# ReflowOvenController.net
KiCad netlist of a schematic drawn in EAGLE
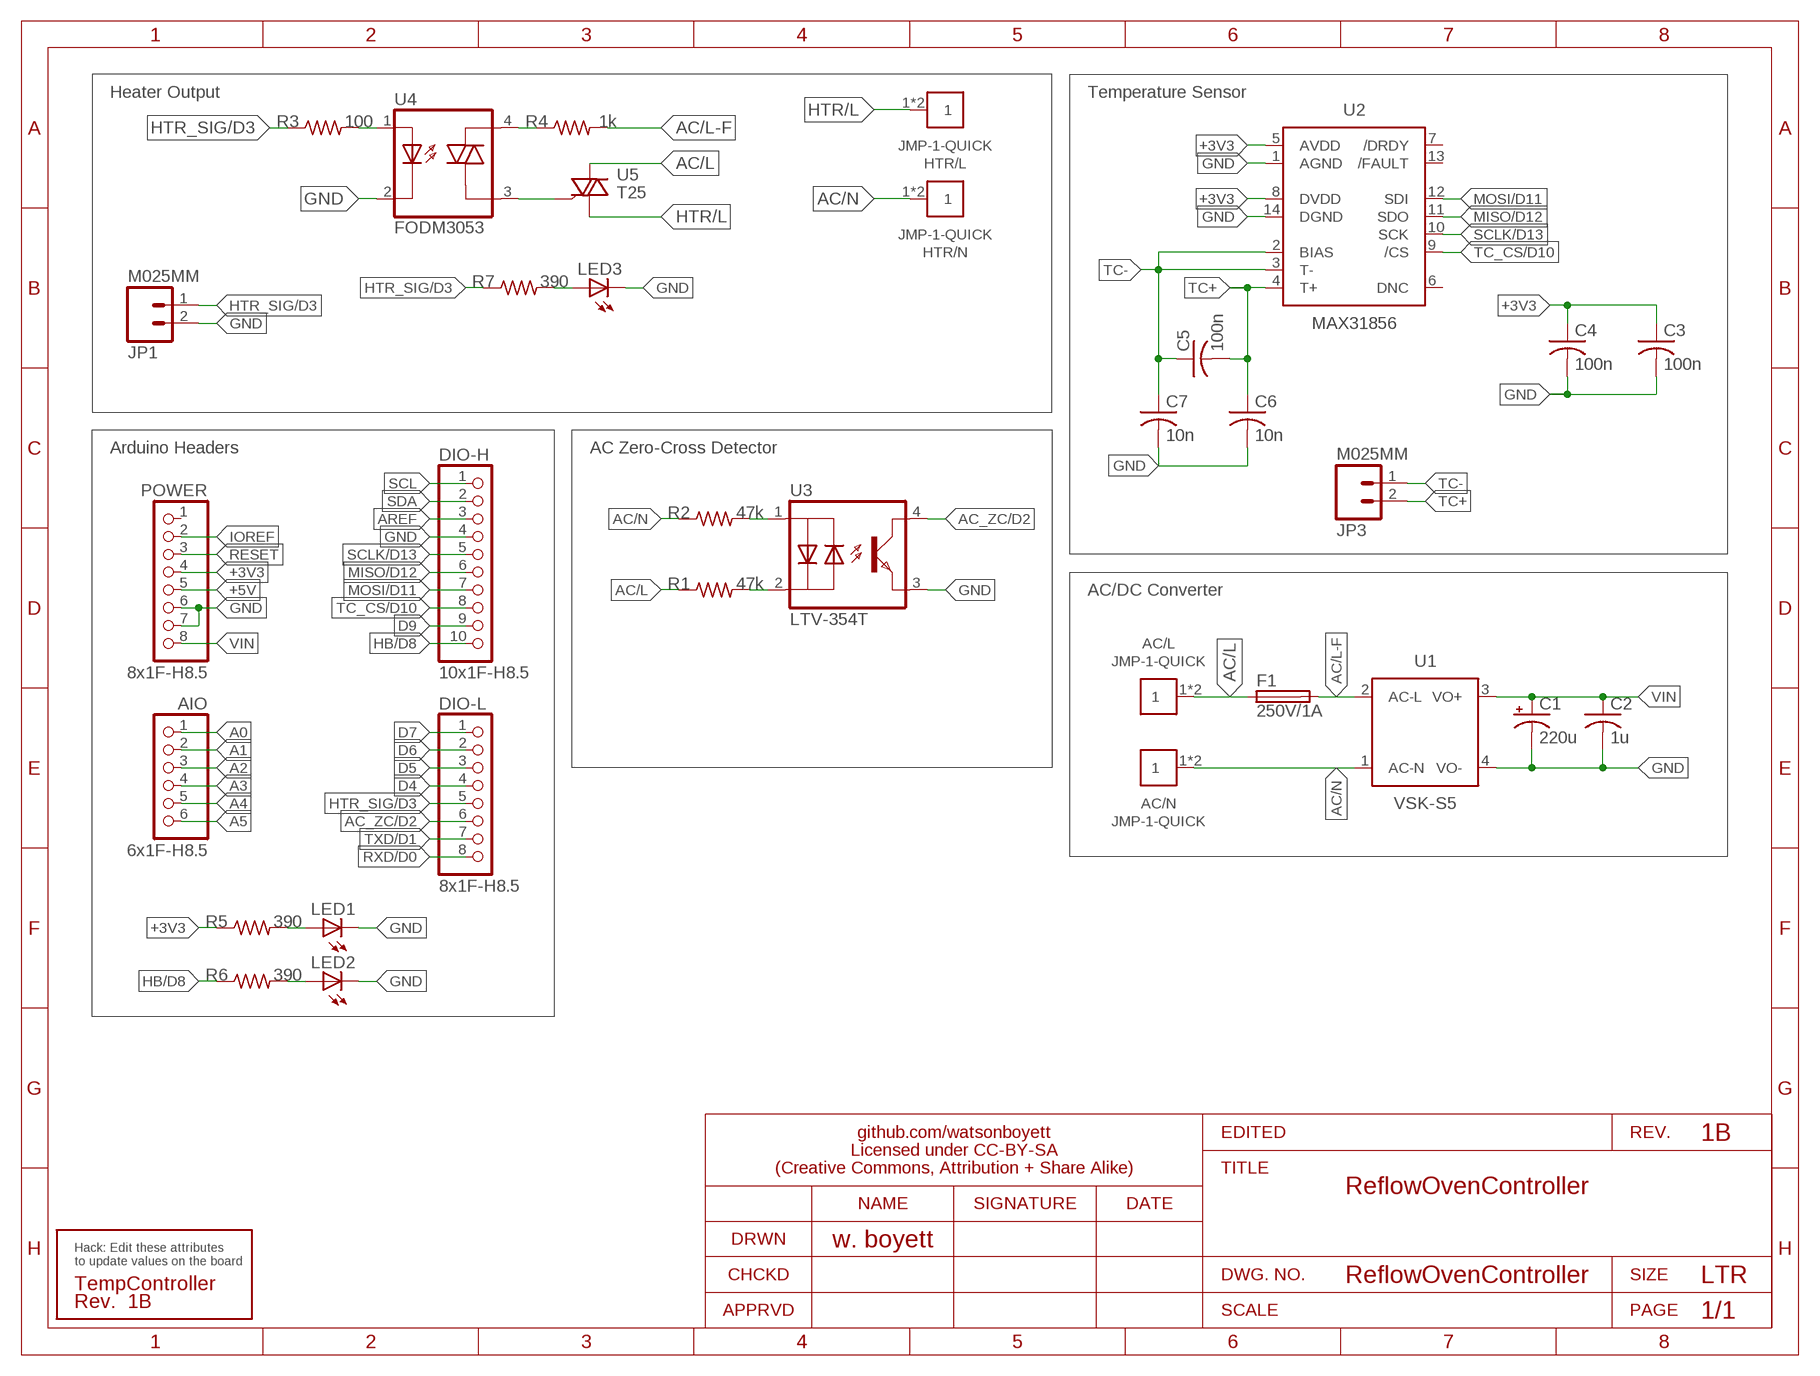
[diagram p0: schematic, sheet 1]

(export (version "E")
  (design (tool "Eeschema 10.0.6"))
  (components
    (comp (ref "AC/L")
      (value "JMP-1-QUICK")
      (footprint "eagle-import:QUICK-1")
      (fields (field (name "MPN") "1287"))
      (libsource (lib "eagle-import") (part "JMP-1-QUICK"))
    )
    (comp (ref "AC/N")
      (value "JMP-1-QUICK")
      (footprint "eagle-import:QUICK-1")
      (fields (field (name "MPN") "1287"))
      (libsource (lib "eagle-import") (part "JMP-1-QUICK"))
    )
    (comp (ref "AIO")
      (value "6x1F-H8.5")
      (footprint "eagle-import:1X06")
      (libsource (lib "eagle-import") (part "PINHD-1X6TH"))
    )
    (comp (ref "C1")
      (value "220u")
      (footprint "eagle-import:153CLV-1014")
      (libsource (lib "eagle-import") (part "CPOL-US153CLV-1014"))
    )
    (comp (ref "C2")
      (value "1u")
      (footprint "eagle-import:C0805")
      (libsource (lib "eagle-import") (part "C-USC0805"))
    )
    (comp (ref "C3")
      (value "100n")
      (footprint "eagle-import:C0805")
      (libsource (lib "eagle-import") (part "C-USC0805"))
    )
    (comp (ref "C4")
      (value "100n")
      (footprint "eagle-import:C0805")
      (libsource (lib "eagle-import") (part "C-USC0805"))
    )
    (comp (ref "C5")
      (value "100n")
      (footprint "eagle-import:C0805")
      (libsource (lib "eagle-import") (part "C-USC0805"))
    )
    (comp (ref "C6")
      (value "10n")
      (footprint "eagle-import:C0805")
      (libsource (lib "eagle-import") (part "C-USC0805"))
    )
    (comp (ref "C7")
      (value "10n")
      (footprint "eagle-import:C0805")
      (libsource (lib "eagle-import") (part "C-USC0805"))
    )
    (comp (ref "DIO-H")
      (value "10x1F-H8.5")
      (footprint "eagle-import:1X10")
      (libsource (lib "eagle-import") (part "PINHD-1X10TH"))
    )
    (comp (ref "DIO-L")
      (value "8x1F-H8.5")
      (footprint "eagle-import:1X08")
      (libsource (lib "eagle-import") (part "PINHD-1X8TH"))
    )
    (comp (ref "F1")
      (value "250V/1A")
      (footprint "eagle-import:2SMD-2410")
      (fields
        (field (name "MPN") "0452004.MRL")
        (field (name "MPN_1") "0454001.MR")
        (field (name "PN-DK") "F3144CT-ND")
      )
      (libsource (lib "eagle-import") (part "FUSE2410"))
    )
    (comp (ref "HTR/L")
      (value "JMP-1-QUICK")
      (footprint "eagle-import:QUICK-1")
      (fields (field (name "MPN") "1287"))
      (libsource (lib "eagle-import") (part "JMP-1-QUICK"))
    )
    (comp (ref "HTR/N")
      (value "JMP-1-QUICK")
      (footprint "eagle-import:QUICK-1")
      (fields (field (name "MPN") "1287"))
      (libsource (lib "eagle-import") (part "JMP-1-QUICK"))
    )
    (comp (ref "JP1")
      (value "M025MM")
      (footprint "eagle-import:SCREWTERMINAL-5MM-2")
      (fields (field (name "MPN") "1729128"))
      (libsource (lib "eagle-import") (part "M025MM"))
    )
    (comp (ref "JP3")
      (value "M025MM")
      (footprint "eagle-import:SCREWTERMINAL-5MM-2")
      (fields (field (name "MPN") "1729128"))
      (libsource (lib "eagle-import") (part "M025MM"))
    )
    (comp (ref "LED1")
      (value "LEDCHIP-LED0805")
      (footprint "eagle-import:CHIP-LED0805")
      (fields (field (name "MPN") "SML-LXT0805IW-TR"))
      (libsource (lib "eagle-import") (part "LEDCHIP-LED0805"))
    )
    (comp (ref "LED2")
      (value "LEDCHIP-LED0805")
      (footprint "eagle-import:CHIP-LED0805")
      (fields (field (name "MPN") "SML-LXT0805IW-TR"))
      (libsource (lib "eagle-import") (part "LEDCHIP-LED0805"))
    )
    (comp (ref "LED3")
      (value "LEDCHIP-LED0805")
      (footprint "eagle-import:CHIP-LED0805")
      (fields (field (name "MPN") "SML-LXT0805IW-TR"))
      (libsource (lib "eagle-import") (part "LEDCHIP-LED0805"))
    )
    (comp (ref "POWER")
      (value "8x1F-H8.5")
      (footprint "eagle-import:1X08")
      (libsource (lib "eagle-import") (part "PINHD-1X8TH"))
    )
    (comp (ref "R1")
      (value "47k")
      (footprint "eagle-import:R1206")
      (libsource (lib "eagle-import") (part "R-US_R1206"))
    )
    (comp (ref "R2")
      (value "47k")
      (footprint "eagle-import:R1206")
      (libsource (lib "eagle-import") (part "R-US_R1206"))
    )
    (comp (ref "R3")
      (value "100")
      (footprint "eagle-import:R0805")
      (libsource (lib "eagle-import") (part "R-US_R0805"))
    )
    (comp (ref "R4")
      (value "1k")
      (footprint "eagle-import:R1206")
      (libsource (lib "eagle-import") (part "R-US_R1206"))
    )
    (comp (ref "R5")
      (value "390")
      (footprint "eagle-import:R0805")
      (libsource (lib "eagle-import") (part "SmslsTron_R-US_R0805"))
    )
    (comp (ref "R6")
      (value "390")
      (footprint "eagle-import:R0805")
      (libsource (lib "eagle-import") (part "SmslsTron_R-US_R0805"))
    )
    (comp (ref "R7")
      (value "390")
      (footprint "eagle-import:R0805")
      (libsource (lib "eagle-import") (part "SmslsTron_R-US_R0805"))
    )
    (comp (ref "U$1")
      (value "SILK_QC")
      (footprint "eagle-import:SILK_QC")
      (fields (field (name "MPN") "DNP") (field (name "PRODUCT") "TempController") (field (name "REV") "1B"))
      (libsource (lib "eagle-import") (part "SILK_QC"))
    )
    (comp (ref "U1")
      (value "VSK-S5")
      (footprint "eagle-import:VSK-S5")
      (libsource (lib "eagle-import") (part "VSK-S5"))
    )
    (comp (ref "U2")
      (value "MAX31856")
      (footprint "eagle-import:TSSOP14")
      (fields (field (name "MPN") "MAX31856MUD+"))
      (libsource (lib "eagle-import") (part "MAX31856"))
    )
    (comp (ref "U3")
      (value "LTV-354T")
      (footprint "eagle-import:SOP-4")
      (libsource (lib "eagle-import") (part "LTV-354T"))
    )
    (comp (ref "U4")
      (value "FODM3053")
      (footprint "eagle-import:SOP-4")
      (fields (field (name "MPN") "FODM3053R2_NF098"))
      (libsource (lib "eagle-import") (part "FODM3053"))
    )
    (comp (ref "U5")
      (value "T25")
      (footprint "eagle-import:TO263-3")
      (libsource (lib "eagle-import") (part "T835-TO263"))
    )
  )
  (nets
    (net (code "1") (name "+3V3") (class "Default")
      (node (ref "C3") (pin "1") (pinfunction "1_1") (pintype "passive"))
      (node (ref "C4") (pin "1") (pinfunction "1_1") (pintype "passive"))
      (node (ref "POWER") (pin "4") (pinfunction "4_4") (pintype "passive"))
      (node (ref "R5") (pin "1") (pinfunction "1_1") (pintype "passive"))
      (node (ref "U2") (pin "5") (pinfunction "AVDD_5") (pintype "power_in"))
      (node (ref "U2") (pin "8") (pinfunction "DVDD_8") (pintype "power_in"))
    )
    (net (code "2") (name "+5V") (class "Default")
      (node (ref "POWER") (pin "5") (pinfunction "5_5") (pintype "passive"))
    )
    (net (code "3") (name "A0") (class "Default")
      (node (ref "AIO") (pin "1") (pinfunction "1_1") (pintype "passive"))
    )
    (net (code "4") (name "A1") (class "Default")
      (node (ref "AIO") (pin "2") (pinfunction "2_2") (pintype "passive"))
    )
    (net (code "5") (name "A2") (class "Default")
      (node (ref "AIO") (pin "3") (pinfunction "3_3") (pintype "passive"))
    )
    (net (code "6") (name "A3") (class "Default")
      (node (ref "AIO") (pin "4") (pinfunction "4_4") (pintype "passive"))
    )
    (net (code "7") (name "A4") (class "Default")
      (node (ref "AIO") (pin "5") (pinfunction "5_5") (pintype "passive"))
    )
    (net (code "8") (name "A5") (class "Default")
      (node (ref "AIO") (pin "6") (pinfunction "6_6") (pintype "passive"))
    )
    (net (code "9") (name "AC_ZC{slash}D2") (class "Default")
      (node (ref "DIO-L") (pin "6") (pinfunction "6_6") (pintype "passive"))
      (node (ref "U3") (pin "4") (pinfunction "COL_4") (pintype "passive"))
    )
    (net (code "10") (name "AC{slash}L") (class "Default")
      (node (ref "AC/L") (pin "1") (pinfunction "1_1") (pintype "bidirectional"))
      (node (ref "AC/L") (pin "2") (pinfunction "1_2") (pintype "bidirectional"))
      (node (ref "F1") (pin "P$1") (pinfunction "1_P$1") (pintype "passive"))
      (node (ref "R1") (pin "1") (pinfunction "1_1") (pintype "passive"))
      (node (ref "U5") (pin "3") (pinfunction "A2_3") (pintype "passive"))
    )
    (net (code "11") (name "AC{slash}L-F") (class "Default")
      (node (ref "F1") (pin "P$2") (pinfunction "2_P$2") (pintype "passive"))
      (node (ref "R4") (pin "2") (pinfunction "2_2") (pintype "passive"))
      (node (ref "U1") (pin "2") (pinfunction "AC-L_2") (pintype "passive"))
    )
    (net (code "12") (name "AC{slash}N") (class "Default")
      (node (ref "AC/N") (pin "1") (pinfunction "1_1") (pintype "bidirectional"))
      (node (ref "AC/N") (pin "2") (pinfunction "1_2") (pintype "bidirectional"))
      (node (ref "HTR/N") (pin "1") (pinfunction "1_1") (pintype "bidirectional"))
      (node (ref "HTR/N") (pin "2") (pinfunction "1_2") (pintype "bidirectional"))
      (node (ref "R2") (pin "1") (pinfunction "1_1") (pintype "passive"))
      (node (ref "U1") (pin "1") (pinfunction "AC-N_1") (pintype "passive"))
    )
    (net (code "13") (name "AREF") (class "Default")
      (node (ref "DIO-H") (pin "3") (pinfunction "3_3") (pintype "passive"))
    )
    (net (code "14") (name "D4") (class "Default")
      (node (ref "DIO-L") (pin "4") (pinfunction "4_4") (pintype "passive"))
    )
    (net (code "15") (name "D5") (class "Default")
      (node (ref "DIO-L") (pin "3") (pinfunction "3_3") (pintype "passive"))
    )
    (net (code "16") (name "D6") (class "Default")
      (node (ref "DIO-L") (pin "2") (pinfunction "2_2") (pintype "passive"))
    )
    (net (code "17") (name "D7") (class "Default")
      (node (ref "DIO-L") (pin "1") (pinfunction "1_1") (pintype "passive"))
    )
    (net (code "18") (name "D9") (class "Default")
      (node (ref "DIO-H") (pin "9") (pinfunction "9_9") (pintype "passive"))
    )
    (net (code "19") (name "GND") (class "Default")
      (node (ref "C1") (pin "-") (pinfunction "-_-") (pintype "passive"))
      (node (ref "C2") (pin "2") (pinfunction "2_2") (pintype "passive"))
      (node (ref "C3") (pin "2") (pinfunction "2_2") (pintype "passive"))
      (node (ref "C4") (pin "2") (pinfunction "2_2") (pintype "passive"))
      (node (ref "C6") (pin "2") (pinfunction "2_2") (pintype "passive"))
      (node (ref "C7") (pin "2") (pinfunction "2_2") (pintype "passive"))
      (node (ref "DIO-H") (pin "4") (pinfunction "4_4") (pintype "passive"))
      (node (ref "JP1") (pin "2") (pinfunction "2_2") (pintype "passive"))
      (node (ref "LED1") (pin "C") (pinfunction "C_C") (pintype "passive"))
      (node (ref "LED2") (pin "C") (pinfunction "C_C") (pintype "passive"))
      (node (ref "LED3") (pin "C") (pinfunction "C_C") (pintype "passive"))
      (node (ref "POWER") (pin "6") (pinfunction "6_6") (pintype "passive"))
      (node (ref "POWER") (pin "7") (pinfunction "7_7") (pintype "passive"))
      (node (ref "U1") (pin "4") (pinfunction "VO-_4") (pintype "passive"))
      (node (ref "U2") (pin "1") (pinfunction "AGND_1") (pintype "power_in"))
      (node (ref "U2") (pin "14") (pinfunction "DGND_14") (pintype "power_in"))
      (node (ref "U3") (pin "3") (pinfunction "EMIT_3") (pintype "passive"))
      (node (ref "U4") (pin "2") (pinfunction "C_2") (pintype "passive"))
    )
    (net (code "20") (name "HB{slash}D8") (class "Default")
      (node (ref "DIO-H") (pin "10") (pinfunction "10_10") (pintype "passive"))
      (node (ref "R6") (pin "1") (pinfunction "1_1") (pintype "passive"))
    )
    (net (code "21") (name "HTR_SIG{slash}D3") (class "Default")
      (node (ref "DIO-L") (pin "5") (pinfunction "5_5") (pintype "passive"))
      (node (ref "JP1") (pin "1") (pinfunction "1_1") (pintype "passive"))
      (node (ref "R3") (pin "1") (pinfunction "1_1") (pintype "passive"))
      (node (ref "R7") (pin "1") (pinfunction "1_1") (pintype "passive"))
    )
    (net (code "22") (name "HTR{slash}L") (class "Default")
      (node (ref "HTR/L") (pin "1") (pinfunction "1_1") (pintype "bidirectional"))
      (node (ref "HTR/L") (pin "2") (pinfunction "1_2") (pintype "bidirectional"))
      (node (ref "U5") (pin "1") (pinfunction "A1_1") (pintype "passive"))
    )
    (net (code "23") (name "IOREF") (class "Default")
      (node (ref "POWER") (pin "2") (pinfunction "2_2") (pintype "passive"))
    )
    (net (code "24") (name "MISO{slash}D12") (class "Default")
      (node (ref "DIO-H") (pin "6") (pinfunction "6_6") (pintype "passive"))
      (node (ref "U2") (pin "11") (pinfunction "SDO_11") (pintype "bidirectional"))
    )
    (net (code "25") (name "MOSI{slash}D11") (class "Default")
      (node (ref "DIO-H") (pin "7") (pinfunction "7_7") (pintype "passive"))
      (node (ref "U2") (pin "12") (pinfunction "SDI_12") (pintype "bidirectional"))
    )
    (net (code "26") (name "Net-(LED1-PadA)") (class "Default")
      (node (ref "LED1") (pin "A") (pinfunction "A_A") (pintype "passive"))
      (node (ref "R5") (pin "2") (pinfunction "2_2") (pintype "passive"))
    )
    (net (code "27") (name "Net-(LED2-PadA)") (class "Default")
      (node (ref "LED2") (pin "A") (pinfunction "A_A") (pintype "passive"))
      (node (ref "R6") (pin "2") (pinfunction "2_2") (pintype "passive"))
    )
    (net (code "28") (name "Net-(LED3-PadA)") (class "Default")
      (node (ref "LED3") (pin "A") (pinfunction "A_A") (pintype "passive"))
      (node (ref "R7") (pin "2") (pinfunction "2_2") (pintype "passive"))
    )
    (net (code "29") (name "Net-(U3-A)") (class "Default")
      (node (ref "R2") (pin "2") (pinfunction "2_2") (pintype "passive"))
      (node (ref "U3") (pin "1") (pinfunction "A_1") (pintype "passive"))
    )
    (net (code "30") (name "Net-(U3-C)") (class "Default")
      (node (ref "R1") (pin "2") (pinfunction "2_2") (pintype "passive"))
      (node (ref "U3") (pin "2") (pinfunction "C_2") (pintype "passive"))
    )
    (net (code "31") (name "Net-(U4-A)") (class "Default")
      (node (ref "R3") (pin "2") (pinfunction "2_2") (pintype "passive"))
      (node (ref "U4") (pin "1") (pinfunction "A_1") (pintype "passive"))
    )
    (net (code "32") (name "Net-(U4-A1)") (class "Default")
      (node (ref "U4") (pin "3") (pinfunction "A1_3") (pintype "passive"))
      (node (ref "U5") (pin "2") (pinfunction "G_2") (pintype "passive"))
    )
    (net (code "33") (name "Net-(U4-A2)") (class "Default")
      (node (ref "R4") (pin "1") (pinfunction "1_1") (pintype "passive"))
      (node (ref "U4") (pin "4") (pinfunction "A2_4") (pintype "passive"))
    )
    (net (code "34") (name "RESET") (class "Default")
      (node (ref "POWER") (pin "3") (pinfunction "3_3") (pintype "passive"))
    )
    (net (code "35") (name "RXD{slash}D0") (class "Default")
      (node (ref "DIO-L") (pin "8") (pinfunction "8_8") (pintype "passive"))
    )
    (net (code "36") (name "SCL") (class "Default")
      (node (ref "DIO-H") (pin "1") (pinfunction "1_1") (pintype "passive"))
    )
    (net (code "37") (name "SCLK{slash}D13") (class "Default")
      (node (ref "DIO-H") (pin "5") (pinfunction "5_5") (pintype "passive"))
      (node (ref "U2") (pin "10") (pinfunction "SCK_10") (pintype "bidirectional"))
    )
    (net (code "38") (name "SDA") (class "Default")
      (node (ref "DIO-H") (pin "2") (pinfunction "2_2") (pintype "passive"))
    )
    (net (code "39") (name "TC+") (class "Default")
      (node (ref "C5") (pin "2") (pinfunction "2_2") (pintype "passive"))
      (node (ref "C6") (pin "1") (pinfunction "1_1") (pintype "passive"))
      (node (ref "JP3") (pin "2") (pinfunction "2_2") (pintype "passive"))
      (node (ref "U2") (pin "4") (pinfunction "T+_4") (pintype "bidirectional"))
    )
    (net (code "40") (name "TC-") (class "Default")
      (node (ref "C5") (pin "1") (pinfunction "1_1") (pintype "passive"))
      (node (ref "C7") (pin "1") (pinfunction "1_1") (pintype "passive"))
      (node (ref "JP3") (pin "1") (pinfunction "1_1") (pintype "passive"))
      (node (ref "U2") (pin "2") (pinfunction "BIAS_2") (pintype "bidirectional"))
      (node (ref "U2") (pin "3") (pinfunction "T-_3") (pintype "bidirectional"))
    )
    (net (code "41") (name "TC_CS{slash}D10") (class "Default")
      (node (ref "DIO-H") (pin "8") (pinfunction "8_8") (pintype "passive"))
      (node (ref "U2") (pin "9") (pinfunction "/CS_9") (pintype "bidirectional"))
    )
    (net (code "42") (name "TXD{slash}D1") (class "Default")
      (node (ref "DIO-L") (pin "7") (pinfunction "7_7") (pintype "passive"))
    )
    (net (code "43") (name "VIN") (class "Default")
      (node (ref "C1") (pin "+") (pinfunction "+_+") (pintype "passive"))
      (node (ref "C2") (pin "1") (pinfunction "1_1") (pintype "passive"))
      (node (ref "POWER") (pin "8") (pinfunction "8_8") (pintype "passive"))
      (node (ref "U1") (pin "3") (pinfunction "VO+_3") (pintype "passive"))
    )
    (net (code "44") (name "unconnected-(POWER-Pad1)") (class "Default")
      (node (ref "POWER") (pin "1") (pinfunction "1_1") (pintype "passive"))
    )
    (net (code "45") (name "unconnected-(U2-DNC-Pad6)") (class "Default")
      (node (ref "U2") (pin "6") (pinfunction "DNC_6") (pintype "no_connect"))
    )
    (net (code "46") (name "unconnected-(U2-{slash}DRDY-Pad7)") (class "Default")
      (node (ref "U2") (pin "7") (pinfunction "/DRDY_7") (pintype "bidirectional"))
    )
    (net (code "47") (name "unconnected-(U2-{slash}FAULT-Pad13)") (class "Default")
      (node (ref "U2") (pin "13") (pinfunction "/FAULT_13") (pintype "bidirectional"))
    )
  )
)
